# schem1.net
KiCad netlist of a schematic drawn in Altium Designer
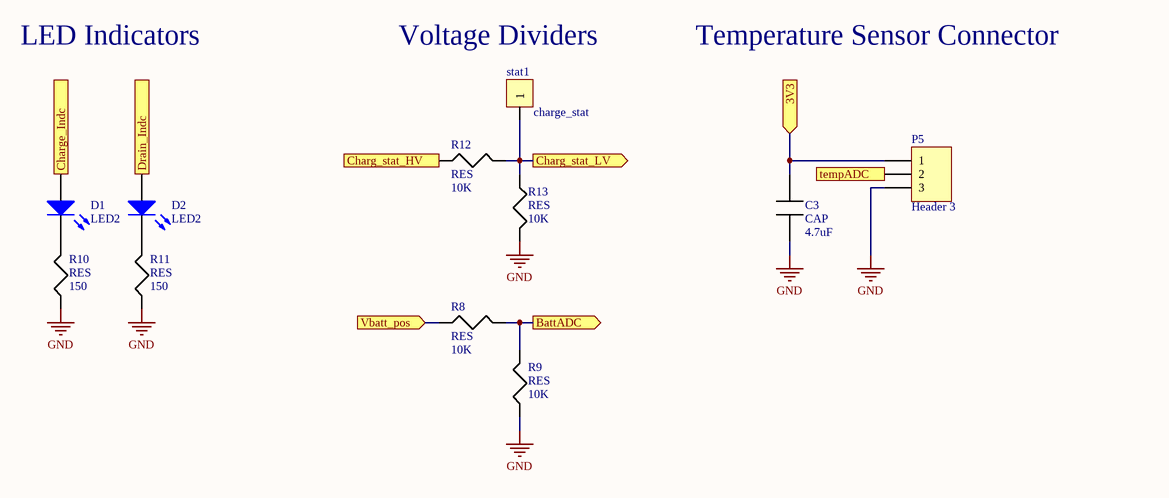
[diagram p0: schem1.SchDoc]

(export (version "E")
  (design (tool "Eeschema 10.0.6"))
  (components
    (comp (ref "C3")
      (value "CAP")
      (footprint "Cap 0603 (1608 metric)")
      (fields (field (name "ALTIUM_VALUE") "4.7uF"))
      (libsource (lib "passives") (part "CAP"))
    )
    (comp (ref "D1")
      (value "LED2")
      (footprint "3.2X1.6X1.1")
      (description "Typical RED, GREEN, YELLOW, AMBER GaAs LED")
      (fields (field (name "PUBLISHER") "Altium Limited"))
      (libsource (lib "Miscellaneous Devices") (part "LED2"))
    )
    (comp (ref "D2")
      (value "LED2")
      (footprint "3.2X1.6X1.1")
      (description "Typical RED, GREEN, YELLOW, AMBER GaAs LED")
      (fields (field (name "PUBLISHER") "Altium Limited"))
      (libsource (lib "Miscellaneous Devices") (part "LED2"))
    )
    (comp (ref "P5")
      (value "Header 3")
      (footprint "HDR1X3")
      (description "Header, 3-Pin")
      (fields (field (name "PUBLISHER") "Altium Limited"))
      (libsource (lib "Miscellaneous Connectors") (part "Header 3"))
    )
    (comp (ref "R8")
      (value "RES")
      (footprint "Res 0603 (1608 metric)")
      (fields (field (name "ALTIUM_VALUE") "10K"))
      (libsource (lib "passives") (part "RES"))
    )
    (comp (ref "R9")
      (value "RES")
      (footprint "Res 0603 (1608 metric)")
      (fields (field (name "ALTIUM_VALUE") "10K"))
      (libsource (lib "passives") (part "RES"))
    )
    (comp (ref "R10")
      (value "RES")
      (footprint "Res 0603 (1608 metric)")
      (fields (field (name "ALTIUM_VALUE") "150"))
      (libsource (lib "passives") (part "RES"))
    )
    (comp (ref "R11")
      (value "RES")
      (footprint "Res 0603 (1608 metric)")
      (fields (field (name "ALTIUM_VALUE") "150"))
      (libsource (lib "passives") (part "RES"))
    )
    (comp (ref "R12")
      (value "RES")
      (footprint "Res 0603 (1608 metric)")
      (fields (field (name "ALTIUM_VALUE") "10K"))
      (libsource (lib "passives") (part "RES"))
    )
    (comp (ref "R13")
      (value "RES")
      (footprint "Res 0603 (1608 metric)")
      (fields (field (name "ALTIUM_VALUE") "10K"))
      (libsource (lib "passives") (part "RES"))
    )
    (comp (ref "stat1")
      (value "charge_stat")
      (footprint "test pad")
      (description "test pad")
      (libsource (lib "test_pad") (part "test_pad"))
    )
  )
  (nets
    (net (code "1") (name "/3V3") (class "Default")
      (node (ref "C3") (pin "2") (pinfunction "2_2") (pintype "passive"))
      (node (ref "P5") (pin "1") (pinfunction "1_1") (pintype "passive"))
    )
    (net (code "2") (name "/BattADC") (class "Default")
      (node (ref "R8") (pin "2") (pinfunction "2_2") (pintype "passive"))
      (node (ref "R9") (pin "2") (pinfunction "2_2") (pintype "passive"))
    )
    (net (code "3") (name "/Charg_stat_HV") (class "Default")
      (node (ref "R12") (pin "1") (pinfunction "1_1") (pintype "passive"))
    )
    (net (code "4") (name "/Charg_stat_LV") (class "Default")
      (node (ref "R12") (pin "2") (pinfunction "2_2") (pintype "passive"))
      (node (ref "R13") (pin "1") (pinfunction "1_1") (pintype "passive"))
      (node (ref "stat1") (pin "1") (pinfunction "1_1") (pintype "passive"))
    )
    (net (code "5") (name "/Charge_Indc") (class "Default")
      (node (ref "D1") (pin "1") (pinfunction "A_1") (pintype "passive"))
    )
    (net (code "6") (name "/Drain_Indc") (class "Default")
      (node (ref "D2") (pin "1") (pinfunction "A_1") (pintype "passive"))
    )
    (net (code "7") (name "/Vbatt_pos") (class "Default")
      (node (ref "R8") (pin "1") (pinfunction "1_1") (pintype "passive"))
    )
    (net (code "8") (name "/tempADC") (class "Default")
      (node (ref "P5") (pin "2") (pinfunction "2_2") (pintype "passive"))
    )
    (net (code "9") (name "GND") (class "Default")
      (node (ref "C3") (pin "1") (pinfunction "1_1") (pintype "passive"))
      (node (ref "P5") (pin "3") (pinfunction "3_3") (pintype "passive"))
      (node (ref "R10") (pin "1") (pinfunction "1_1") (pintype "passive"))
      (node (ref "R11") (pin "1") (pinfunction "1_1") (pintype "passive"))
      (node (ref "R13") (pin "2") (pinfunction "2_2") (pintype "passive"))
      (node (ref "R9") (pin "1") (pinfunction "1_1") (pintype "passive"))
    )
    (net (code "10") (name "Net-(D1-K)") (class "Default")
      (node (ref "D1") (pin "2") (pinfunction "K_2") (pintype "passive"))
      (node (ref "R10") (pin "2") (pinfunction "2_2") (pintype "passive"))
    )
    (net (code "11") (name "Net-(D2-K)") (class "Default")
      (node (ref "D2") (pin "2") (pinfunction "K_2") (pintype "passive"))
      (node (ref "R11") (pin "2") (pinfunction "2_2") (pintype "passive"))
    )
  )
)
